# vgattiny85_single_v1.net
KiCad netlist of a schematic drawn in EAGLE
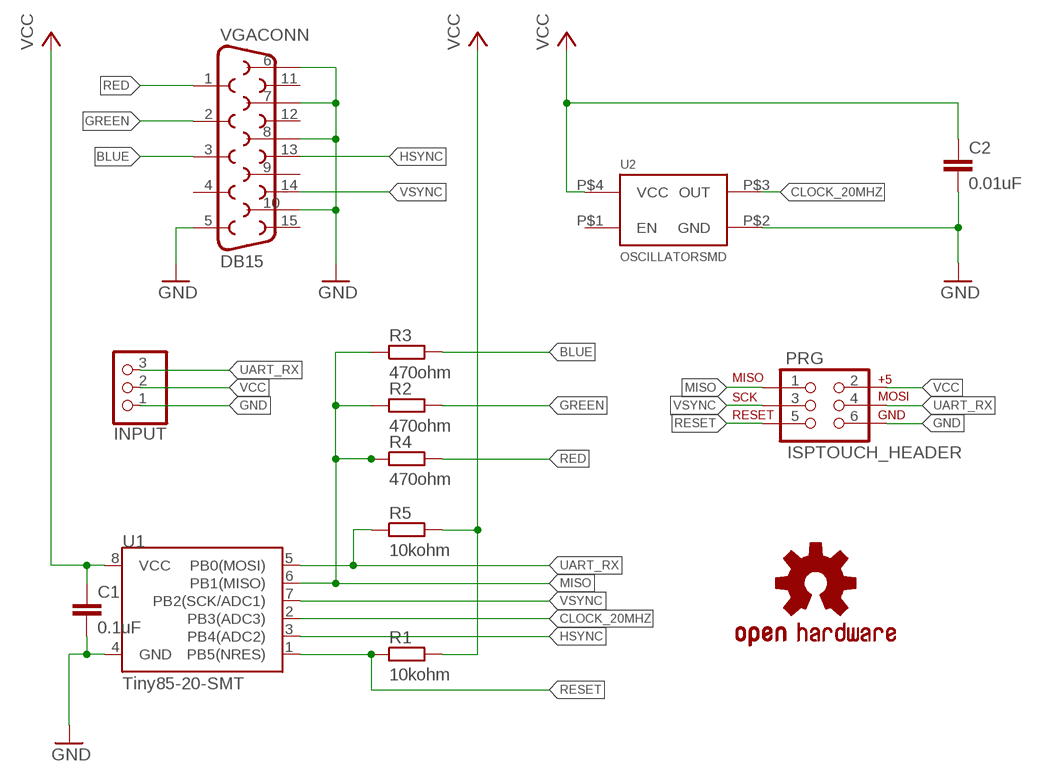
[diagram p0: schematic, sheet 1]

(export (version "E")
  (design (tool "Eeschema 10.0.6"))
  (components
    (comp (ref "C1")
      (value "0.1uF")
      (footprint "eagle-import:0603-CAP")
      (libsource (lib "eagle-import") (part "CAP0603-CAP"))
    )
    (comp (ref "C2")
      (value "0.01uF")
      (footprint "eagle-import:0603-CAP")
      (libsource (lib "eagle-import") (part "CAP0603-CAP"))
    )
    (comp (ref "INPUT")
      (value "PINHD-1X03_2.54-S")
      (footprint "eagle-import:1X03-S")
      (libsource (lib "eagle-import") (part "PINHD-1X03_2.54-S"))
    )
    (comp (ref "LOGO1")
      (value "OSHW-LOGOS")
      (footprint "eagle-import:OSHW-LOGO-S")
      (libsource (lib "eagle-import") (part "OSHW-LOGOS"))
    )
    (comp (ref "PRG")
      (value "ISPTOUCH_HEADER")
      (footprint "eagle-import:AVX_9188_6-WAY_MATING_GUIDE")
      (libsource (lib "eagle-import") (part "ISPTOUCH_HEADER"))
    )
    (comp (ref "R1")
      (value "10kohm")
      (footprint "eagle-import:R0603")
      (libsource (lib "eagle-import") (part "RESISTOR"))
    )
    (comp (ref "R2")
      (value "470ohm")
      (footprint "eagle-import:R0603")
      (libsource (lib "eagle-import") (part "RESISTOR"))
    )
    (comp (ref "R3")
      (value "470ohm")
      (footprint "eagle-import:R0603")
      (libsource (lib "eagle-import") (part "RESISTOR"))
    )
    (comp (ref "R4")
      (value "470ohm")
      (footprint "eagle-import:R0603")
      (libsource (lib "eagle-import") (part "RESISTOR"))
    )
    (comp (ref "R5")
      (value "10kohm")
      (footprint "eagle-import:R0603")
      (libsource (lib "eagle-import") (part "RESISTOR"))
    )
    (comp (ref "U1")
      (value "Tiny85-20-SMT")
      (footprint "eagle-import:SO08-EIAJ")
      (libsource (lib "eagle-import") (part "ATTINY45TINY85-20-SMT"))
    )
    (comp (ref "U2")
      (value "OSCILLATORSMD")
      (footprint "eagle-import:CRYSTAL-SMD-7X5")
      (libsource (lib "eagle-import") (part "OSCILLATORSMD"))
    )
    (comp (ref "VGACONN")
      (value "DB15")
      (footprint "eagle-import:DB15")
      (libsource (lib "eagle-import") (part "DB15"))
    )
  )
  (nets
    (net (code "1") (name "BLUE") (class "Default")
      (node (ref "R3") (pin "2") (pinfunction "2_2") (pintype "passive"))
      (node (ref "VGACONN") (pin "3") (pinfunction "3_3") (pintype "passive"))
    )
    (net (code "2") (name "CLOCK_20MHZ") (class "Default")
      (node (ref "U1") (pin "2") (pinfunction "PB3(ADC3)_2") (pintype "bidirectional"))
      (node (ref "U2") (pin "P$3") (pinfunction "OUT_P$3") (pintype "bidirectional"))
    )
    (net (code "3") (name "GND") (class "Default")
      (node (ref "C1") (pin "2") (pinfunction "2_2") (pintype "passive"))
      (node (ref "C2") (pin "2") (pinfunction "2_2") (pintype "passive"))
      (node (ref "INPUT") (pin "1") (pinfunction "1_1") (pintype "passive"))
      (node (ref "PRG") (pin "6") (pinfunction "6_6") (pintype "passive"))
      (node (ref "U1") (pin "4") (pinfunction "GND_4") (pintype "bidirectional"))
      (node (ref "U2") (pin "P$2") (pinfunction "GND_P$2") (pintype "bidirectional"))
      (node (ref "VGACONN") (pin "10") (pinfunction "10_10") (pintype "passive"))
      (node (ref "VGACONN") (pin "5") (pinfunction "5_5") (pintype "passive"))
      (node (ref "VGACONN") (pin "6") (pinfunction "6_6") (pintype "passive"))
      (node (ref "VGACONN") (pin "7") (pinfunction "7_7") (pintype "passive"))
      (node (ref "VGACONN") (pin "8") (pinfunction "8_8") (pintype "passive"))
    )
    (net (code "4") (name "GREEN") (class "Default")
      (node (ref "R2") (pin "2") (pinfunction "2_2") (pintype "passive"))
      (node (ref "VGACONN") (pin "2") (pinfunction "2_2") (pintype "passive"))
    )
    (net (code "5") (name "HSYNC") (class "Default")
      (node (ref "U1") (pin "3") (pinfunction "PB4(ADC2)_3") (pintype "bidirectional"))
      (node (ref "VGACONN") (pin "13") (pinfunction "13_13") (pintype "passive"))
    )
    (net (code "6") (name "MISO") (class "Default")
      (node (ref "PRG") (pin "1") (pinfunction "1_1") (pintype "passive"))
      (node (ref "R2") (pin "1") (pinfunction "1_1") (pintype "passive"))
      (node (ref "R3") (pin "1") (pinfunction "1_1") (pintype "passive"))
      (node (ref "R4") (pin "1") (pinfunction "1_1") (pintype "passive"))
      (node (ref "U1") (pin "6") (pinfunction "PB1(MISO)_6") (pintype "bidirectional"))
    )
    (net (code "7") (name "RED") (class "Default")
      (node (ref "R4") (pin "2") (pinfunction "2_2") (pintype "passive"))
      (node (ref "VGACONN") (pin "1") (pinfunction "1_1") (pintype "passive"))
    )
    (net (code "8") (name "RESET") (class "Default")
      (node (ref "PRG") (pin "5") (pinfunction "5_5") (pintype "passive"))
      (node (ref "R1") (pin "1") (pinfunction "1_1") (pintype "passive"))
      (node (ref "U1") (pin "1") (pinfunction "PB5(NRES)_1") (pintype "bidirectional"))
    )
    (net (code "9") (name "UART_RX") (class "Default")
      (node (ref "INPUT") (pin "3") (pinfunction "3_3") (pintype "passive"))
      (node (ref "PRG") (pin "4") (pinfunction "4_4") (pintype "passive"))
      (node (ref "R5") (pin "1") (pinfunction "1_1") (pintype "passive"))
      (node (ref "U1") (pin "5") (pinfunction "PB0(MOSI)_5") (pintype "bidirectional"))
    )
    (net (code "10") (name "VCC") (class "Default")
      (node (ref "C1") (pin "1") (pinfunction "1_1") (pintype "passive"))
      (node (ref "C2") (pin "1") (pinfunction "1_1") (pintype "passive"))
      (node (ref "INPUT") (pin "2") (pinfunction "2_2") (pintype "passive"))
      (node (ref "PRG") (pin "2") (pinfunction "2_2") (pintype "passive"))
      (node (ref "R1") (pin "2") (pinfunction "2_2") (pintype "passive"))
      (node (ref "R5") (pin "2") (pinfunction "2_2") (pintype "passive"))
      (node (ref "U1") (pin "8") (pinfunction "VCC_8") (pintype "bidirectional"))
      (node (ref "U2") (pin "P$4") (pinfunction "VCC_P$4") (pintype "bidirectional"))
    )
    (net (code "11") (name "VSYNC") (class "Default")
      (node (ref "PRG") (pin "3") (pinfunction "3_3") (pintype "passive"))
      (node (ref "U1") (pin "7") (pinfunction "PB2(SCK/ADC1)_7") (pintype "bidirectional"))
      (node (ref "VGACONN") (pin "14") (pinfunction "14_14") (pintype "passive"))
    )
    (net (code "12") (name "unconnected-(U2-EN-PadP$1)") (class "Default")
      (node (ref "U2") (pin "P$1") (pinfunction "EN_P$1") (pintype "bidirectional"))
    )
    (net (code "13") (name "unconnected-(VGACONN-Pad4)") (class "Default")
      (node (ref "VGACONN") (pin "4") (pinfunction "4_4") (pintype "passive"))
    )
    (net (code "14") (name "unconnected-(VGACONN-Pad9)") (class "Default")
      (node (ref "VGACONN") (pin "9") (pinfunction "9_9") (pintype "passive"))
    )
    (net (code "15") (name "unconnected-(VGACONN-Pad11)") (class "Default")
      (node (ref "VGACONN") (pin "11") (pinfunction "11_11") (pintype "passive"))
    )
    (net (code "16") (name "unconnected-(VGACONN-Pad12)") (class "Default")
      (node (ref "VGACONN") (pin "12") (pinfunction "12_12") (pintype "passive"))
    )
    (net (code "17") (name "unconnected-(VGACONN-Pad15)") (class "Default")
      (node (ref "VGACONN") (pin "15") (pinfunction "15_15") (pintype "passive"))
    )
  )
)
